# CPU.net
KiCad netlist of a schematic drawn in Altium Designer
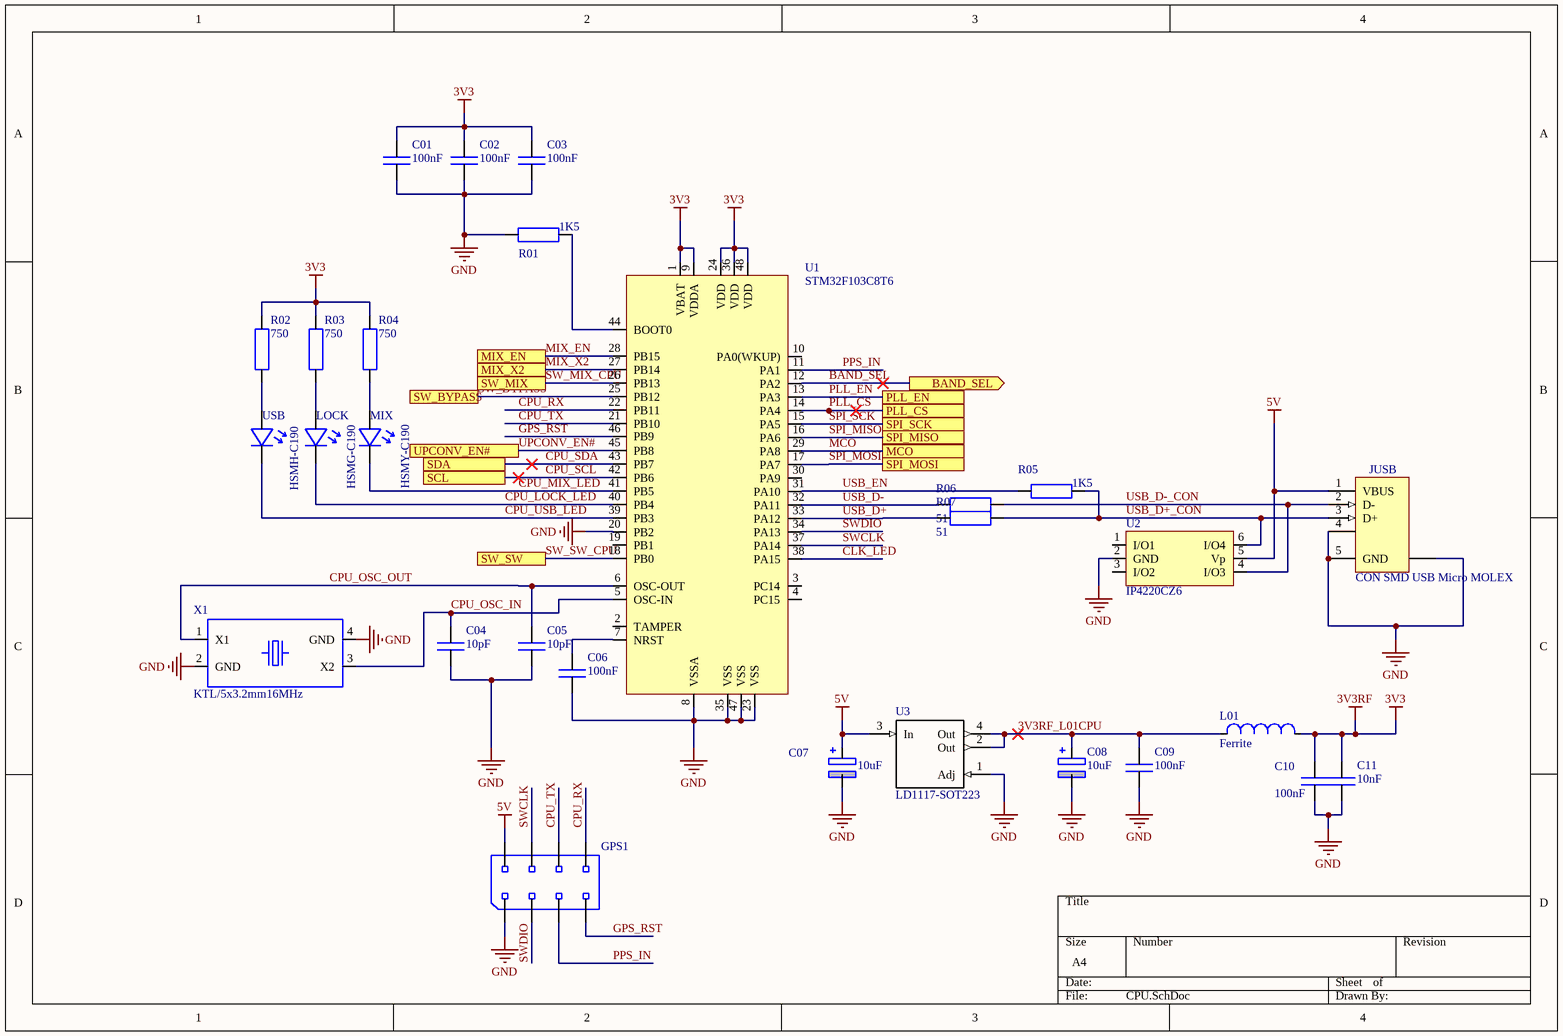
[diagram p0: CPU.SchDoc]

(export (version "E")
  (design (tool "Eeschema 10.0.6"))
  (components
    (comp (ref "C01")
      (value "100nF")
      (footprint "smd C0603_0.80")
      (description "smd capaciteit, verp.0603, 100nF")
      (fields (field (name "PART NUMBER") "CSMD603/100nF"))
      (libsource (lib "CDE_Library") (part "CSMD603/100nF"))
    )
    (comp (ref "C02")
      (value "100nF")
      (footprint "smd C0603_0.80")
      (description "smd capaciteit, verp.0603, 100nF")
      (fields (field (name "PART NUMBER") "CSMD603/100nF"))
      (libsource (lib "CDE_Library") (part "CSMD603/100nF"))
    )
    (comp (ref "C03")
      (value "100nF")
      (footprint "smd C0603_0.80")
      (description "smd capaciteit, verp.0603, 100nF")
      (fields (field (name "PART NUMBER") "CSMD603/100nF"))
      (libsource (lib "CDE_Library") (part "CSMD603/100nF"))
    )
    (comp (ref "C04")
      (value "10pF")
      (footprint "smd C0603_0.80")
      (description "smd capaciteit, verp.0603, 10pF")
      (fields (field (name "PART NUMBER") "CSMD603/10pF"))
      (libsource (lib "CDE_Library") (part "CSMD603/10pF"))
    )
    (comp (ref "C05")
      (value "10pF")
      (footprint "smd C0603_0.80")
      (description "smd capaciteit, verp.0603, 10pF")
      (fields (field (name "PART NUMBER") "CSMD603/10pF"))
      (libsource (lib "CDE_Library") (part "CSMD603/10pF"))
    )
    (comp (ref "C06")
      (value "100nF")
      (footprint "smd C0603_0.80")
      (description "smd capaciteit, verp.0603, 100nF")
      (fields (field (name "PART NUMBER") "CSMD603/100nF"))
      (libsource (lib "CDE_Library") (part "CSMD603/100nF"))
    )
    (comp (ref "C07")
      (value "10uF")
      (footprint "smd C1206 polar")
      (description "smd capaciteit, tantalium, verp.1206, 10uF/10V")
      (fields (field (name "PART NUMBER") "CSMD1206/10uF/10V"))
      (libsource (lib "CDE_Library") (part "CSMD1206/10uF/10V"))
    )
    (comp (ref "C08")
      (value "10uF")
      (footprint "smd C1206 polar")
      (description "smd capaciteit, tantalium, verp.1206, 10uF/10V")
      (fields (field (name "PART NUMBER") "CSMD1206/10uF/10V"))
      (libsource (lib "CDE_Library") (part "CSMD1206/10uF/10V"))
    )
    (comp (ref "C09")
      (value "100nF")
      (footprint "smd C0603_0.80")
      (description "smd capaciteit, verp.0603, 100nF")
      (fields (field (name "PART NUMBER") "CSMD603/100nF"))
      (libsource (lib "CDE_Library") (part "CSMD603/100nF"))
    )
    (comp (ref "C10")
      (value "100nF")
      (footprint "smd C0603_0.80")
      (description "smd capaciteit, verp.0603, 100nF")
      (fields (field (name "PART NUMBER") "CSMD603/100nF"))
      (libsource (lib "CDE_Library") (part "CSMD603/100nF"))
    )
    (comp (ref "C11")
      (value "10nF")
      (footprint "smd C0603_0.80")
      (description "smd capaciteit, verp.0603, 10nF")
      (fields (field (name "PART NUMBER") "CSMD603/10nF"))
      (libsource (lib "CDE_Library") (part "CSMD603/10nF"))
    )
    (comp (ref "GPS1")
      (value "~")
      (footprint "hdr 2x4")
      (description "pcb header recht 2x4  pitch 100mil")
      (fields (field (name "PART NUMBER") "CON HDR 2x4"))
      (libsource (lib "CDE_Library") (part "CON HDR 2x4"))
    )
    (comp (ref "JUSB")
      (value "CON SMD USB Micro MOLEX")
      (footprint "SMD USB MOLEX")
      (description "MOLEX - 47589-0001 - MICRO USB TYPE AB")
      (libsource (lib "CDE_Library") (part "CON SMD USB Micro MOLEX"))
    )
    (comp (ref "L01")
      (value "Ferrite")
      (footprint "smd C0805")
      (description "Ferrite bead, 0805 package")
      (libsource (lib "CDE_Library") (part "Ferrite 0805"))
    )
    (comp (ref "LOCK")
      (value "HSMG-C190")
      (footprint "led HSMH-C190 (Avago Technologies)")
      (description "led smd groen, Avago Techn., HSMG-C190")
      (libsource (lib "CDE_Library") (part "HSMG-C190"))
    )
    (comp (ref "MIX")
      (value "HSMY-C190")
      (footprint "led HSMH-C190 (Avago Technologies)")
      (description "led smd geel, Avago Techn., HSMY-C190")
      (libsource (lib "CDE_Library") (part "HSMY-C190"))
    )
    (comp (ref "R01")
      (value "1K5")
      (footprint "smd C0603_0.45")
      (description "weerstand SMD603, 1K5")
      (libsource (lib "CDE_Library") (part "1K5/603"))
    )
    (comp (ref "R02")
      (value "750")
      (footprint "smd C0603_0.45")
      (description "weerstand SMD603, 750R")
      (libsource (lib "CDE_Library") (part "750R/603"))
    )
    (comp (ref "R03")
      (value "750")
      (footprint "smd C0603_0.45")
      (description "weerstand SMD603, 750R")
      (libsource (lib "CDE_Library") (part "750R/603"))
    )
    (comp (ref "R04")
      (value "750")
      (footprint "smd C0603_0.45")
      (description "weerstand SMD603, 750R")
      (libsource (lib "CDE_Library") (part "750R/603"))
    )
    (comp (ref "R05")
      (value "1K5")
      (footprint "smd C0603_0.45")
      (description "weerstand SMD603, 1K5")
      (libsource (lib "CDE_Library") (part "1K5/603"))
    )
    (comp (ref "R06")
      (value "51")
      (footprint "smd C0603_0.45")
      (description "weerstand SMD603, 51R")
      (libsource (lib "CDE_Library") (part "51R/603"))
    )
    (comp (ref "R07")
      (value "51")
      (footprint "smd C0603_0.45")
      (description "weerstand SMD603, 51R")
      (libsource (lib "CDE_Library") (part "51R/603"))
    )
    (comp (ref "U1")
      (value "STM32F103C8T6")
      (footprint "TSQFP50P900X900X160-48N")
      (libsource (lib "library") (part "STM32F100xx"))
    )
    (comp (ref "U2")
      (value "IP4220CZ6")
      (footprint "smd SOT-457")
      (description "Dual USB 2.0 integrated ESD protection")
      (libsource (lib "CDE_Library") (part "IP4220CZ6"))
    )
    (comp (ref "U3")
      (value "LD1117-SOT223")
      (footprint "SOT223")
      (libsource (lib "vh_altium_library") (part "LD1117-SOT223"))
    )
    (comp (ref "USB")
      (value "HSMH-C190")
      (footprint "led HSMH-C190 (Avago Technologies)")
      (description "led smd rood, Avago Techn., HSMH-C190")
      (libsource (lib "CDE_Library") (part "HSMH-C190"))
    )
    (comp (ref "X1")
      (value "KTL/5x3.2mm16MHz")
      (footprint "smd KTL 5x3.2")
      (description "TXC Xtal 16.000 MHz, 5x3.2mm")
      (fields (field (name "PART NUMBER") "KTL/5x3.2mm 16MHz"))
      (libsource (lib "CDE_Library_local") (part "KTL/5x3.2mm 16MHz"))
    )
  )
  (nets
    (net (code "2") (name "/3V3RF_L01CPU") (class "Default")
      (node (ref "C08") (pin "1") (pintype "passive"))
      (node (ref "C09") (pin "2") (pintype "passive"))
      (node (ref "L01") (pin "1") (pintype "passive"))
      (node (ref "U3") (pin "2") (pinfunction "Out_2") (pintype "output"))
      (node (ref "U3") (pin "4") (pinfunction "Out_4") (pintype "output"))
    )
    (net (code "3") (name "/BAND_SEL") (class "Default")
      (node (ref "U1") (pin "12") (pinfunction "PA2_12") (pintype "passive"))
    )
    (net (code "4") (name "/CLK_LED") (class "Default")
      (node (ref "U1") (pin "38") (pinfunction "PA15_38") (pintype "passive"))
    )
    (net (code "5") (name "/CPU_LOCK_LED") (class "Default")
      (node (ref "LOCK") (pin "2") (pintype "passive"))
      (node (ref "U1") (pin "40") (pinfunction "PB4_40") (pintype "passive"))
    )
    (net (code "6") (name "/CPU_MIX_LED") (class "Default")
      (node (ref "MIX") (pin "2") (pintype "passive"))
      (node (ref "U1") (pin "41") (pinfunction "PB5_41") (pintype "passive"))
    )
    (net (code "7") (name "/CPU_OSC_IN") (class "Default")
      (node (ref "C04") (pin "2") (pintype "passive"))
      (node (ref "U1") (pin "5") (pinfunction "OSC-IN_5") (pintype "passive"))
      (node (ref "X1") (pin "3") (pinfunction "X2_3") (pintype "passive"))
    )
    (net (code "8") (name "/CPU_OSC_OUT") (class "Default")
      (node (ref "C05") (pin "2") (pintype "passive"))
      (node (ref "U1") (pin "6") (pinfunction "OSC-OUT_6") (pintype "passive"))
      (node (ref "X1") (pin "1") (pinfunction "X1_1") (pintype "passive"))
    )
    (net (code "9") (name "/CPU_RX") (class "Default")
      (node (ref "GPS1") (pin "8") (pintype "passive"))
      (node (ref "U1") (pin "22") (pinfunction "PB11_22") (pintype "passive"))
    )
    (net (code "10") (name "/CPU_SCL") (class "Default")
      (node (ref "U1") (pin "42") (pinfunction "PB6_42") (pintype "passive"))
    )
    (net (code "11") (name "/CPU_SDA") (class "Default")
      (node (ref "U1") (pin "43") (pinfunction "PB7_43") (pintype "passive"))
    )
    (net (code "12") (name "/CPU_TX") (class "Default")
      (node (ref "GPS1") (pin "6") (pintype "passive"))
      (node (ref "U1") (pin "21") (pinfunction "PB10_21") (pintype "passive"))
    )
    (net (code "13") (name "/CPU_USB_LED") (class "Default")
      (node (ref "U1") (pin "39") (pinfunction "PB3_39") (pintype "passive"))
      (node (ref "USB") (pin "2") (pintype "passive"))
    )
    (net (code "14") (name "/GPS_RST") (class "Default")
      (node (ref "GPS1") (pin "7") (pintype "passive"))
      (node (ref "U1") (pin "46") (pinfunction "PB9_46") (pintype "passive"))
    )
    (net (code "15") (name "/MCO") (class "Default")
      (node (ref "U1") (pin "29") (pinfunction "PA8_29") (pintype "passive"))
    )
    (net (code "16") (name "/MIX_EN") (class "Default")
      (node (ref "U1") (pin "28") (pinfunction "PB15_28") (pintype "passive"))
    )
    (net (code "17") (name "/MIX_X2") (class "Default")
      (node (ref "U1") (pin "27") (pinfunction "PB14_27") (pintype "passive"))
    )
    (net (code "18") (name "/PLL_CS") (class "Default")
      (node (ref "U1") (pin "14") (pinfunction "PA4_14") (pintype "passive"))
    )
    (net (code "19") (name "/PLL_EN") (class "Default")
      (node (ref "U1") (pin "13") (pinfunction "PA3_13") (pintype "passive"))
    )
    (net (code "20") (name "/PPS_IN") (class "Default")
      (node (ref "GPS1") (pin "5") (pintype "passive"))
      (node (ref "U1") (pin "11") (pinfunction "PA1_11") (pintype "passive"))
    )
    (net (code "21") (name "/SPI_MISO") (class "Default")
      (node (ref "U1") (pin "16") (pinfunction "PA6_16") (pintype "passive"))
    )
    (net (code "22") (name "/SPI_MOSI") (class "Default")
      (node (ref "U1") (pin "17") (pinfunction "PA7_17") (pintype "passive"))
    )
    (net (code "23") (name "/SPI_SCK") (class "Default")
      (node (ref "U1") (pin "15") (pinfunction "PA5_15") (pintype "passive"))
    )
    (net (code "24") (name "/SWCLK") (class "Default")
      (node (ref "GPS1") (pin "4") (pintype "passive"))
      (node (ref "U1") (pin "37") (pinfunction "PA14_37") (pintype "passive"))
    )
    (net (code "25") (name "/SWDIO") (class "Default")
      (node (ref "GPS1") (pin "3") (pintype "passive"))
      (node (ref "U1") (pin "34") (pinfunction "PA13_34") (pintype "passive"))
    )
    (net (code "26") (name "/SW_BYPASS") (class "Default")
      (node (ref "U1") (pin "25") (pinfunction "PB12_25") (pintype "passive"))
    )
    (net (code "27") (name "/SW_MIX_CPU") (class "Default")
      (node (ref "U1") (pin "26") (pinfunction "PB13_26") (pintype "passive"))
    )
    (net (code "28") (name "/SW_SW_CPU") (class "Default")
      (node (ref "U1") (pin "18") (pinfunction "PB0_18") (pintype "passive"))
    )
    (net (code "29") (name "/UPCONV_EN#") (class "Default")
      (node (ref "U1") (pin "45") (pinfunction "PB8_45") (pintype "passive"))
    )
    (net (code "30") (name "/USB_D+") (class "Default")
      (node (ref "R07") (pin "1") (pintype "passive"))
      (node (ref "U1") (pin "33") (pinfunction "PA12_33") (pintype "passive"))
    )
    (net (code "31") (name "/USB_D+_CON") (class "Default")
      (node (ref "JUSB") (pin "3") (pinfunction "D+_3") (pintype "input"))
      (node (ref "R05") (pin "2") (pintype "passive"))
      (node (ref "R07") (pin "2") (pintype "passive"))
      (node (ref "U2") (pin "6") (pinfunction "I/O4_6") (pintype "passive"))
    )
    (net (code "32") (name "/USB_D-") (class "Default")
      (node (ref "R06") (pin "1") (pintype "passive"))
      (node (ref "U1") (pin "32") (pinfunction "PA11_32") (pintype "passive"))
    )
    (net (code "33") (name "/USB_D-_CON") (class "Default")
      (node (ref "JUSB") (pin "2") (pinfunction "D-_2") (pintype "input"))
      (node (ref "R06") (pin "2") (pintype "passive"))
      (node (ref "U2") (pin "4") (pinfunction "I/O3_4") (pintype "passive"))
    )
    (net (code "34") (name "/USB_EN") (class "Default")
      (node (ref "R05") (pin "1") (pintype "passive"))
      (node (ref "U1") (pin "31") (pinfunction "PA10_31") (pintype "passive"))
    )
    (net (code "35") (name "3V3") (class "Default")
      (node (ref "C01") (pin "2") (pintype "passive"))
      (node (ref "C02") (pin "2") (pintype "passive"))
      (node (ref "C03") (pin "2") (pintype "passive"))
      (node (ref "C10") (pin "2") (pintype "passive"))
      (node (ref "C11") (pin "2") (pintype "passive"))
      (node (ref "L01") (pin "2") (pintype "passive"))
      (node (ref "R02") (pin "2") (pintype "passive"))
      (node (ref "R03") (pin "2") (pintype "passive"))
      (node (ref "R04") (pin "2") (pintype "passive"))
      (node (ref "U1") (pin "1") (pinfunction "VBAT_1") (pintype "passive"))
      (node (ref "U1") (pin "24") (pinfunction "VDD_24") (pintype "passive"))
      (node (ref "U1") (pin "36") (pinfunction "VDD_36") (pintype "passive"))
      (node (ref "U1") (pin "48") (pinfunction "VDD_48") (pintype "passive"))
      (node (ref "U1") (pin "9") (pinfunction "VDDA_9") (pintype "passive"))
    )
    (net (code "36") (name "5V") (class "Default")
      (node (ref "C07") (pin "1") (pintype "passive"))
      (node (ref "GPS1") (pin "2") (pintype "passive"))
      (node (ref "JUSB") (pin "1") (pinfunction "VBUS_1") (pintype "power_in"))
      (node (ref "U2") (pin "5") (pinfunction "Vp_5") (pintype "passive"))
      (node (ref "U3") (pin "3") (pinfunction "In_3") (pintype "input"))
    )
    (net (code "37") (name "GND") (class "Default")
      (node (ref "C01") (pin "1") (pintype "passive"))
      (node (ref "C02") (pin "1") (pintype "passive"))
      (node (ref "C03") (pin "1") (pintype "passive"))
      (node (ref "C04") (pin "1") (pintype "passive"))
      (node (ref "C05") (pin "1") (pintype "passive"))
      (node (ref "C06") (pin "1") (pintype "passive"))
      (node (ref "C07") (pin "2") (pintype "passive"))
      (node (ref "C08") (pin "2") (pintype "passive"))
      (node (ref "C09") (pin "1") (pintype "passive"))
      (node (ref "C10") (pin "1") (pintype "passive"))
      (node (ref "C11") (pin "1") (pintype "passive"))
      (node (ref "GPS1") (pin "1") (pintype "passive"))
      (node (ref "JUSB") (pin "4") (pinfunction "GND_4") (pintype "power_in"))
      (node (ref "JUSB") (pin "5") (pinfunction "GND_5") (pintype "passive"))
      (node (ref "JUSB") (pin "6") (pinfunction "SHLD_6") (pintype "passive"))
      (node (ref "R01") (pin "1") (pintype "passive"))
      (node (ref "U1") (pin "20") (pinfunction "PB2_20") (pintype "passive"))
      (node (ref "U1") (pin "23") (pinfunction "VSS_23") (pintype "passive"))
      (node (ref "U1") (pin "35") (pinfunction "VSS_35") (pintype "passive"))
      (node (ref "U1") (pin "47") (pinfunction "VSS_47") (pintype "passive"))
      (node (ref "U1") (pin "8") (pinfunction "VSSA_8") (pintype "passive"))
      (node (ref "U2") (pin "2") (pinfunction "GND_2") (pintype "passive"))
      (node (ref "U3") (pin "1") (pinfunction "Adj_1") (pintype "input"))
      (node (ref "X1") (pin "2") (pinfunction "GND_2") (pintype "passive"))
      (node (ref "X1") (pin "4") (pinfunction "GND_4") (pintype "passive"))
    )
    (net (code "38") (name "Net-(LOCK-Pad1)") (class "Default")
      (node (ref "LOCK") (pin "1") (pintype "passive"))
      (node (ref "R03") (pin "1") (pintype "passive"))
    )
    (net (code "39") (name "Net-(MIX-Pad1)") (class "Default")
      (node (ref "MIX") (pin "1") (pintype "passive"))
      (node (ref "R04") (pin "1") (pintype "passive"))
    )
    (net (code "40") (name "Net-(R02-Pad1)") (class "Default")
      (node (ref "R02") (pin "1") (pintype "passive"))
      (node (ref "USB") (pin "1") (pintype "passive"))
    )
    (net (code "41") (name "Net-(U1-BOOT0)") (class "Default")
      (node (ref "R01") (pin "2") (pintype "passive"))
      (node (ref "U1") (pin "44") (pinfunction "BOOT0_44") (pintype "passive"))
    )
    (net (code "42") (name "Net-(U1-NRST)") (class "Default")
      (node (ref "C06") (pin "2") (pintype "passive"))
      (node (ref "U1") (pin "7") (pinfunction "NRST_7") (pintype "passive"))
    )
    (net (code "43") (name "unconnected-(U1-PA0(WKUP)-Pad10)") (class "Default")
      (node (ref "U1") (pin "10") (pinfunction "PA0(WKUP)_10") (pintype "passive"))
    )
    (net (code "44") (name "unconnected-(U1-PA9-Pad30)") (class "Default")
      (node (ref "U1") (pin "30") (pinfunction "PA9_30") (pintype "passive"))
    )
    (net (code "45") (name "unconnected-(U1-PB1-Pad19)") (class "Default")
      (node (ref "U1") (pin "19") (pinfunction "PB1_19") (pintype "passive"))
    )
    (net (code "46") (name "unconnected-(U1-PC14-Pad3)") (class "Default")
      (node (ref "U1") (pin "3") (pinfunction "PC14_3") (pintype "passive"))
    )
    (net (code "47") (name "unconnected-(U1-PC15-Pad4)") (class "Default")
      (node (ref "U1") (pin "4") (pinfunction "PC15_4") (pintype "passive"))
    )
    (net (code "48") (name "unconnected-(U1-TAMPER-Pad2)") (class "Default")
      (node (ref "U1") (pin "2") (pinfunction "TAMPER_2") (pintype "passive"))
    )
    (net (code "49") (name "unconnected-(U2-I{slash}O1-Pad1)") (class "Default")
      (node (ref "U2") (pin "1") (pinfunction "I/O1_1") (pintype "passive"))
    )
    (net (code "50") (name "unconnected-(U2-I{slash}O2-Pad3)") (class "Default")
      (node (ref "U2") (pin "3") (pinfunction "I/O2_3") (pintype "passive"))
    )
  )
)
